# AVR.net
KiCad netlist of a schematic drawn in Altium Designer
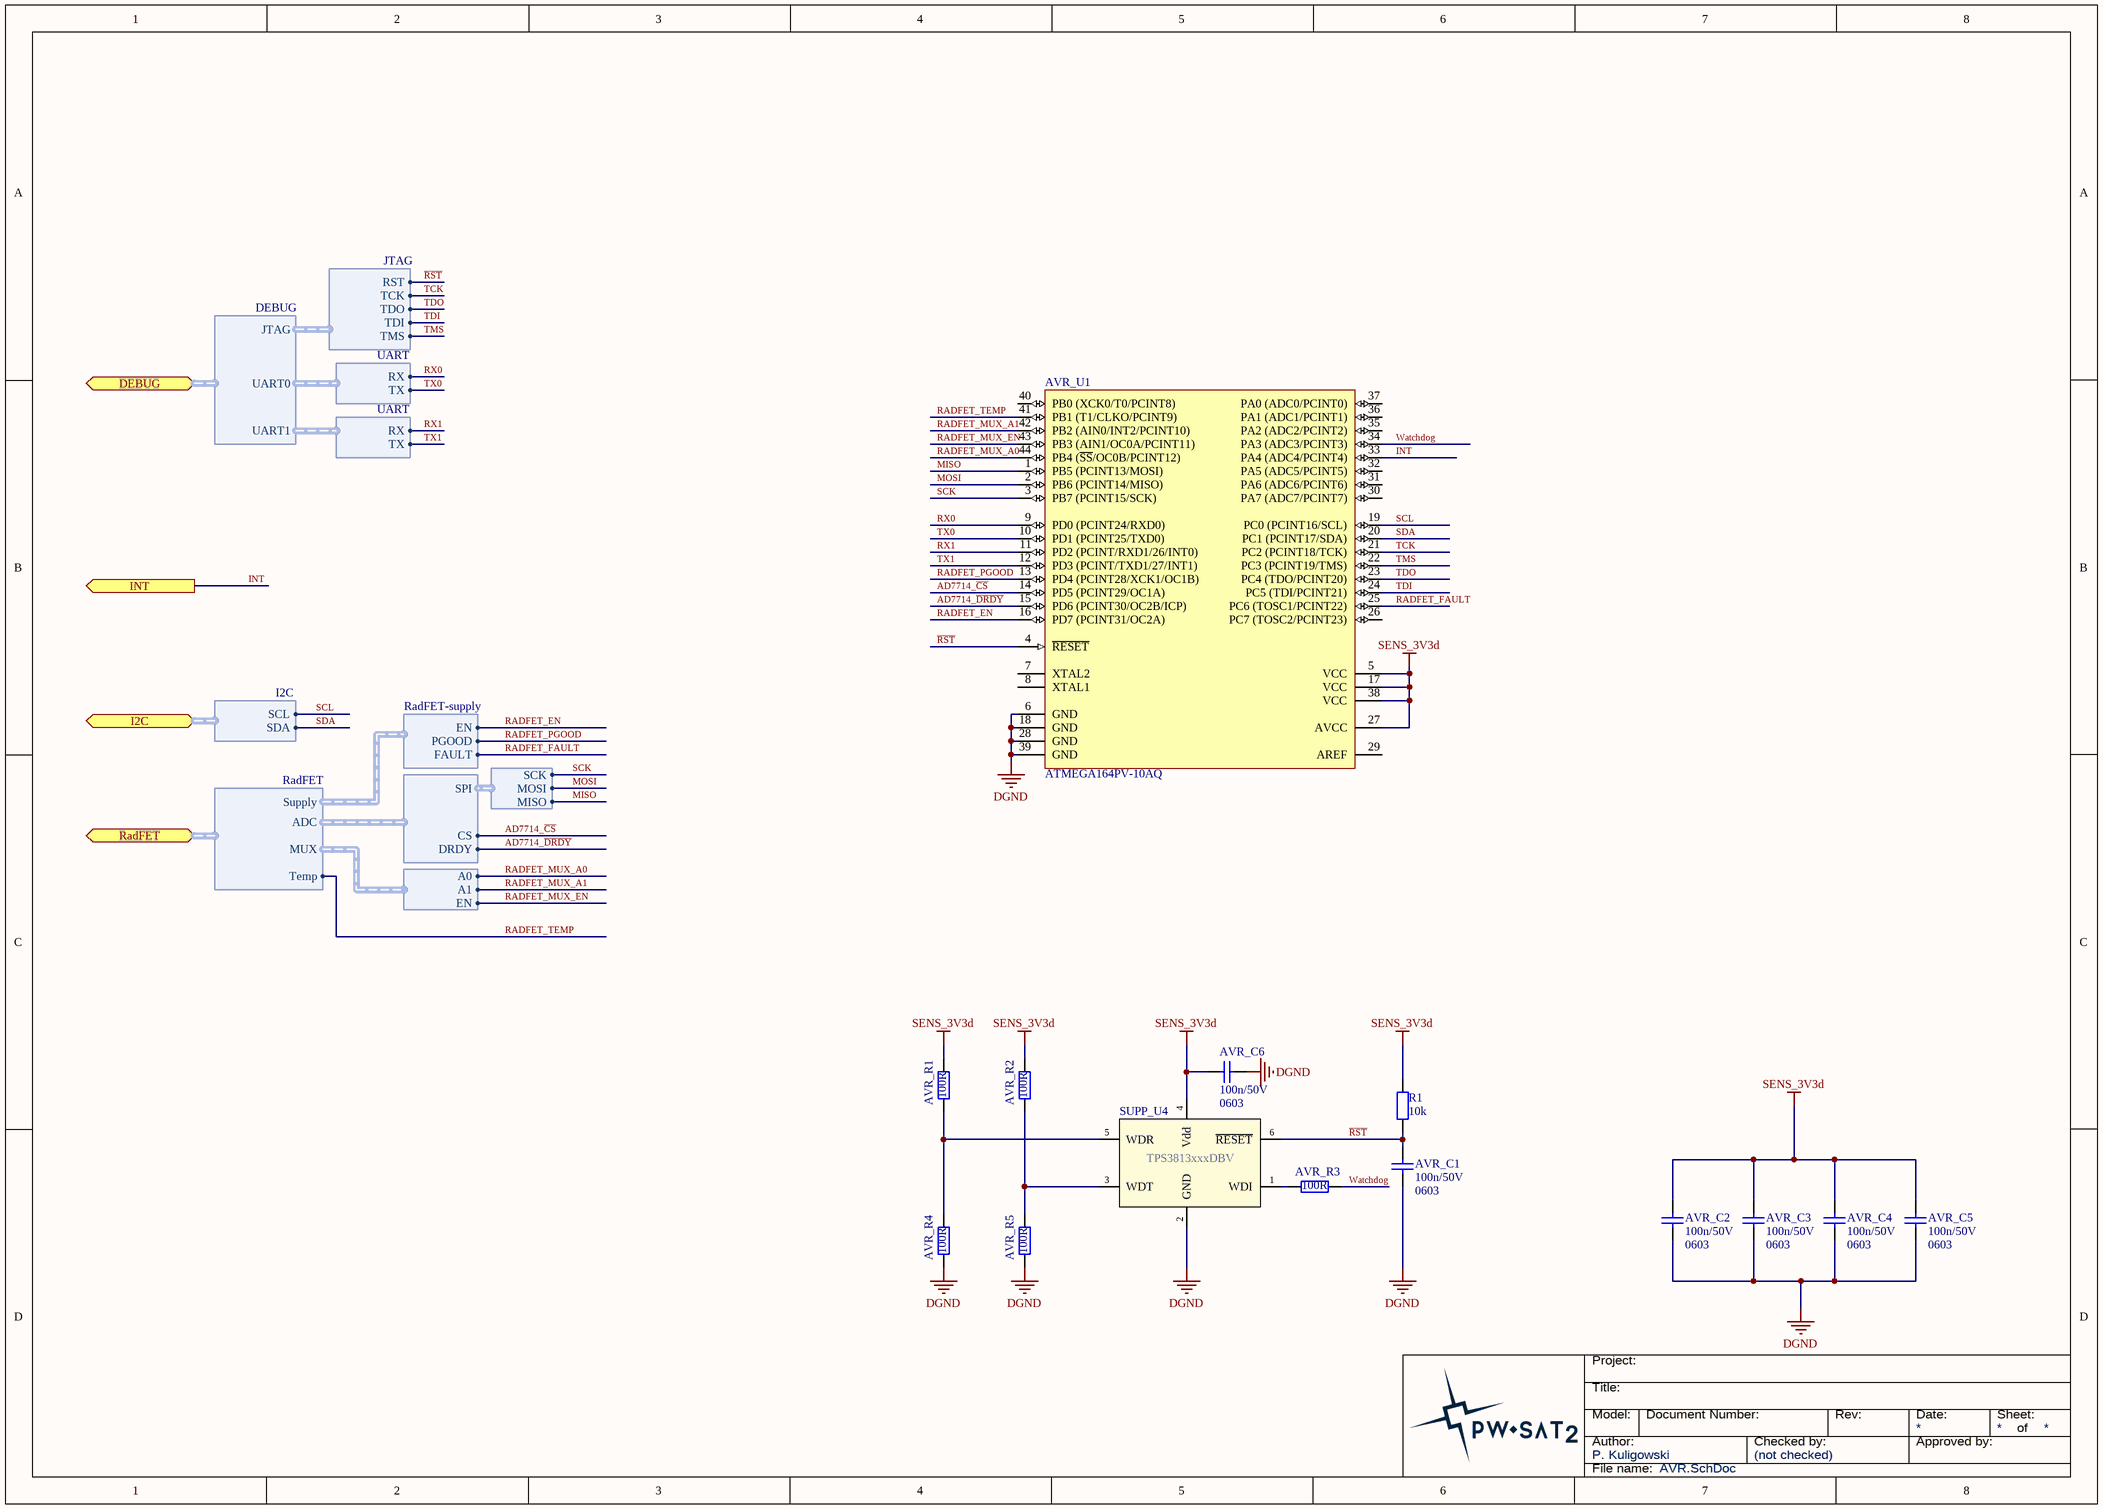
[diagram p0: AVR.SchDoc]

(export (version "E")
  (design (tool "Eeschema 10.0.6"))
  (components
    (comp (ref "AVR_C1")
      (value "100n/50V")
      (footprint "SMD_Capacitor_0603")
      (description "Ceramic Cap Kemet COTS 100n/50V X7R 0603")
      (fields
        (field (name "MANUFACTURER") "Kemet")
        (field (name "MANUFACTURERPARTNUMBER") "C0603T104K5RALTU")
        (field (name "PACKAGE") "0603")
      )
      (libsource (lib "capacitors") (part "Cer_C0603T104K5RALTU"))
    )
    (comp (ref "AVR_C2")
      (value "100n/50V")
      (footprint "SMD_Capacitor_0603")
      (description "Ceramic Cap Kemet COTS 100n/50V X7R 0603")
      (fields
        (field (name "MANUFACTURER") "Kemet")
        (field (name "MANUFACTURERPARTNUMBER") "C0603T104K5RALTU")
        (field (name "PACKAGE") "0603")
      )
      (libsource (lib "capacitors") (part "Cer_C0603T104K5RALTU"))
    )
    (comp (ref "AVR_C3")
      (value "100n/50V")
      (footprint "SMD_Capacitor_0603")
      (description "Ceramic Cap Kemet COTS 100n/50V X7R 0603")
      (fields
        (field (name "MANUFACTURER") "Kemet")
        (field (name "MANUFACTURERPARTNUMBER") "C0603T104K5RALTU")
        (field (name "PACKAGE") "0603")
      )
      (libsource (lib "capacitors") (part "Cer_C0603T104K5RALTU"))
    )
    (comp (ref "AVR_C4")
      (value "100n/50V")
      (footprint "SMD_Capacitor_0603")
      (description "Ceramic Cap Kemet COTS 100n/50V X7R 0603")
      (fields
        (field (name "MANUFACTURER") "Kemet")
        (field (name "MANUFACTURERPARTNUMBER") "C0603T104K5RALTU")
        (field (name "PACKAGE") "0603")
      )
      (libsource (lib "capacitors") (part "Cer_C0603T104K5RALTU"))
    )
    (comp (ref "AVR_C5")
      (value "100n/50V")
      (footprint "SMD_Capacitor_0603")
      (description "Ceramic Cap Kemet COTS 100n/50V X7R 0603")
      (fields
        (field (name "MANUFACTURER") "Kemet")
        (field (name "MANUFACTURERPARTNUMBER") "C0603T104K5RALTU")
        (field (name "PACKAGE") "0603")
      )
      (libsource (lib "capacitors") (part "Cer_C0603T104K5RALTU"))
    )
    (comp (ref "AVR_C6")
      (value "100n/50V")
      (footprint "SMD_Capacitor_0603")
      (description "Ceramic Cap Kemet COTS 100n/50V X7R 0603")
      (fields
        (field (name "MANUFACTURER") "Kemet")
        (field (name "MANUFACTURERPARTNUMBER") "C0603T104K5RALTU")
        (field (name "PACKAGE") "0603")
      )
      (libsource (lib "capacitors") (part "Cer_C0603T104K5RALTU"))
    )
    (comp (ref "AVR_R1")
      (value "100R")
      (footprint "SMD_Resistor_0603")
      (libsource (lib "resistors") (part "Res"))
    )
    (comp (ref "AVR_R2")
      (value "100R")
      (footprint "SMD_Resistor_0603")
      (libsource (lib "resistors") (part "Res"))
    )
    (comp (ref "AVR_R3") (value "100R") (footprint "SMD_Resistor_0603") (libsource (lib "") (part "Res_1")))
    (comp (ref "AVR_R4")
      (value "100R")
      (footprint "SMD_Resistor_0603")
      (libsource (lib "resistors") (part "Res"))
    )
    (comp (ref "AVR_R5")
      (value "100R")
      (footprint "SMD_Resistor_0603")
      (libsource (lib "resistors") (part "Res"))
    )
    (comp (ref "AVR_U1")
      (value "ATMEGA164PV-10AQ")
      (footprint "TQFP-44")
      (description "General-purpose microcontroller")
      (libsource (lib "microcircuits") (part "ATMEGA164PV-10AQ"))
    )
    (comp (ref "R1")
      (value "10k")
      (footprint "SMD_Resistor_0603")
      (description "10k/1% Vishay CRCW 0603 Resistor. 100mW, 100ppm, 75V.")
      (fields
        (field (name "MANUFACTURER") "Vishay")
        (field (name "MANUFACTURERPARTNUMBER") "CRCW060310K0FKxxxx")
      )
      (libsource (lib "resistors") (part "CRCW060310K0FKxxxx"))
    )
    (comp (ref "SUPP_U4")
      (value "TPS3813xxxDBV")
      (footprint "SOT23-6")
      (description "Processor Supervisory Circuits with Window-Watchdog.")
      (fields (field (name "MANUFACTURER") "Texas Instruments"))
      (libsource (lib "microcircuits") (part "TPS3813xxxDBV"))
    )
  )
  (nets
    (net (code "10") (name "/AD7714_~{CS}") (class "Default")
      (node (ref "AVR_U1") (pin "14") (pinfunction "PD5_(PCINT29/OC1A)_14") (pintype "bidirectional"))
    )
    (net (code "11") (name "/AD7714_~{DRDY}") (class "Default")
      (node (ref "AVR_U1") (pin "15") (pinfunction "PD6_(PCINT30/OC2B/ICP)_15") (pintype "bidirectional"))
    )
    (net (code "13") (name "/INT") (class "Default")
      (node (ref "AVR_U1") (pin "33") (pinfunction "PA4_(ADC4/PCINT4)_33") (pintype "bidirectional"))
    )
    (net (code "14") (name "/MISO") (class "Default")
      (node (ref "AVR_U1") (pin "1") (pinfunction "PB5_(PCINT13/MOSI)_1") (pintype "bidirectional"))
    )
    (net (code "15") (name "/MOSI") (class "Default")
      (node (ref "AVR_U1") (pin "2") (pinfunction "PB6_(PCINT14/MISO)_2") (pintype "bidirectional"))
    )
    (net (code "16") (name "/RADFET_EN") (class "Default")
      (node (ref "AVR_U1") (pin "16") (pinfunction "PD7_(PCINT31/OC2A)_16") (pintype "bidirectional"))
    )
    (net (code "17") (name "/RADFET_FAULT") (class "Default")
      (node (ref "AVR_U1") (pin "25") (pinfunction "PC6_(TOSC1/PCINT22)_25") (pintype "bidirectional"))
    )
    (net (code "18") (name "/RADFET_MUX_A0") (class "Default")
      (node (ref "AVR_U1") (pin "44") (pinfunction "PB4_(~{SS}/OC0B/PCINT12)_44") (pintype "bidirectional"))
    )
    (net (code "19") (name "/RADFET_MUX_A1") (class "Default")
      (node (ref "AVR_U1") (pin "42") (pinfunction "PB2_(AIN0/INT2/PCINT10)_42") (pintype "bidirectional"))
    )
    (net (code "20") (name "/RADFET_MUX_EN") (class "Default")
      (node (ref "AVR_U1") (pin "43") (pinfunction "PB3_(AIN1/OC0A/PCINT11)_43") (pintype "bidirectional"))
    )
    (net (code "21") (name "/RADFET_PGOOD") (class "Default")
      (node (ref "AVR_U1") (pin "13") (pinfunction "PD4_(PCINT28/XCK1/OC1B)_13") (pintype "bidirectional"))
    )
    (net (code "22") (name "/RADFET_TEMP") (class "Default")
      (node (ref "AVR_U1") (pin "41") (pinfunction "PB1_(T1/CLKO/PCINT9)_41") (pintype "bidirectional"))
    )
    (net (code "23") (name "/RX0") (class "Default")
      (node (ref "AVR_U1") (pin "9") (pinfunction "PD0_(PCINT24/RXD0)_9") (pintype "bidirectional"))
    )
    (net (code "24") (name "/RX1") (class "Default")
      (node (ref "AVR_U1") (pin "11") (pinfunction "PD2_(PCINT/RXD1/26/INT0)_11") (pintype "bidirectional"))
    )
    (net (code "26") (name "/SCK") (class "Default")
      (node (ref "AVR_U1") (pin "3") (pinfunction "PB7_(PCINT15/SCK)_3") (pintype "bidirectional"))
    )
    (net (code "27") (name "/SCL") (class "Default")
      (node (ref "AVR_U1") (pin "19") (pinfunction "PC0_(PCINT16/SCL)_19") (pintype "bidirectional"))
    )
    (net (code "28") (name "/SDA") (class "Default")
      (node (ref "AVR_U1") (pin "20") (pinfunction "PC1_(PCINT17/SDA)_20") (pintype "bidirectional"))
    )
    (net (code "29") (name "/TCK") (class "Default")
      (node (ref "AVR_U1") (pin "21") (pinfunction "PC2_(PCINT18/TCK)_21") (pintype "bidirectional"))
    )
    (net (code "30") (name "/TDI") (class "Default")
      (node (ref "AVR_U1") (pin "24") (pinfunction "PC5_(TDI/PCINT21)_24") (pintype "bidirectional"))
    )
    (net (code "31") (name "/TDO") (class "Default")
      (node (ref "AVR_U1") (pin "23") (pinfunction "PC4_(TDO/PCINT20)_23") (pintype "bidirectional"))
    )
    (net (code "32") (name "/TMS") (class "Default")
      (node (ref "AVR_U1") (pin "22") (pinfunction "PC3_(PCINT19/TMS)_22") (pintype "bidirectional"))
    )
    (net (code "33") (name "/TX0") (class "Default")
      (node (ref "AVR_U1") (pin "10") (pinfunction "PD1_(PCINT25/TXD0)_10") (pintype "bidirectional"))
    )
    (net (code "34") (name "/TX1") (class "Default")
      (node (ref "AVR_U1") (pin "12") (pinfunction "PD3_(PCINT/TXD1/27/INT1)_12") (pintype "bidirectional"))
    )
    (net (code "35") (name "/Watchdog") (class "Default")
      (node (ref "AVR_R3") (pin "2") (pinfunction "2_2") (pintype "passive"))
      (node (ref "AVR_U1") (pin "34") (pinfunction "PA3_(ADC3/PCINT3)_34") (pintype "bidirectional"))
    )
    (net (code "43") (name "/~{RST}") (class "Default")
      (node (ref "AVR_C1") (pin "1") (pinfunction "1_1") (pintype "passive"))
      (node (ref "AVR_U1") (pin "4") (pinfunction "~{RESET}_4") (pintype "input"))
      (node (ref "R1") (pin "2") (pinfunction "2_2") (pintype "passive"))
      (node (ref "SUPP_U4") (pin "6") (pinfunction "~{RESET}_6") (pintype "passive"))
    )
    (net (code "44") (name "DGND") (class "Default")
      (node (ref "AVR_C1") (pin "2") (pinfunction "2_2") (pintype "passive"))
      (node (ref "AVR_C2") (pin "2") (pinfunction "2_2") (pintype "passive"))
      (node (ref "AVR_C3") (pin "2") (pinfunction "2_2") (pintype "passive"))
      (node (ref "AVR_C4") (pin "2") (pinfunction "2_2") (pintype "passive"))
      (node (ref "AVR_C5") (pin "2") (pinfunction "2_2") (pintype "passive"))
      (node (ref "AVR_C6") (pin "2") (pinfunction "2_2") (pintype "passive"))
      (node (ref "AVR_R4") (pin "2") (pinfunction "2_2") (pintype "passive"))
      (node (ref "AVR_R5") (pin "2") (pinfunction "2_2") (pintype "passive"))
      (node (ref "AVR_U1") (pin "18") (pinfunction "GND_18") (pintype "power_in"))
      (node (ref "AVR_U1") (pin "28") (pinfunction "GND_28") (pintype "power_in"))
      (node (ref "AVR_U1") (pin "39") (pinfunction "GND_39") (pintype "power_in"))
      (node (ref "AVR_U1") (pin "6") (pinfunction "GND_6") (pintype "power_in"))
      (node (ref "SUPP_U4") (pin "2") (pinfunction "GND_2") (pintype "passive"))
    )
    (net (code "45") (name "Net-(SUPP_U4-WDI)") (class "Default")
      (node (ref "AVR_R3") (pin "1") (pinfunction "1_1") (pintype "passive"))
      (node (ref "SUPP_U4") (pin "1") (pinfunction "WDI_1") (pintype "passive"))
    )
    (net (code "46") (name "Net-(SUPP_U4-WDR)") (class "Default")
      (node (ref "AVR_R1") (pin "2") (pinfunction "2_2") (pintype "passive"))
      (node (ref "AVR_R4") (pin "1") (pinfunction "1_1") (pintype "passive"))
      (node (ref "SUPP_U4") (pin "5") (pinfunction "WDR_5") (pintype "passive"))
    )
    (net (code "47") (name "Net-(SUPP_U4-WDT)") (class "Default")
      (node (ref "AVR_R2") (pin "2") (pinfunction "2_2") (pintype "passive"))
      (node (ref "AVR_R5") (pin "1") (pinfunction "1_1") (pintype "passive"))
      (node (ref "SUPP_U4") (pin "3") (pinfunction "WDT_3") (pintype "passive"))
    )
    (net (code "48") (name "SENS_3V3d") (class "Default")
      (node (ref "AVR_C2") (pin "1") (pinfunction "1_1") (pintype "passive"))
      (node (ref "AVR_C3") (pin "1") (pinfunction "1_1") (pintype "passive"))
      (node (ref "AVR_C4") (pin "1") (pinfunction "1_1") (pintype "passive"))
      (node (ref "AVR_C5") (pin "1") (pinfunction "1_1") (pintype "passive"))
      (node (ref "AVR_C6") (pin "1") (pinfunction "1_1") (pintype "passive"))
      (node (ref "AVR_R1") (pin "1") (pinfunction "1_1") (pintype "passive"))
      (node (ref "AVR_R2") (pin "1") (pinfunction "1_1") (pintype "passive"))
      (node (ref "AVR_U1") (pin "17") (pinfunction "VCC_17") (pintype "power_in"))
      (node (ref "AVR_U1") (pin "27") (pinfunction "AVCC_27") (pintype "power_in"))
      (node (ref "AVR_U1") (pin "38") (pinfunction "VCC_38") (pintype "power_in"))
      (node (ref "AVR_U1") (pin "5") (pinfunction "VCC_5") (pintype "power_in"))
      (node (ref "R1") (pin "1") (pinfunction "1_1") (pintype "passive"))
      (node (ref "SUPP_U4") (pin "4") (pinfunction "Vdd_4") (pintype "passive"))
    )
    (net (code "49") (name "unconnected-(AVR_U1-AREF-Pad29)") (class "Default")
      (node (ref "AVR_U1") (pin "29") (pinfunction "AREF_29") (pintype "power_in"))
    )
    (net (code "50") (name "unconnected-(AVR_U1-PA0_(ADC0{slash}PCINT0)-Pad37)") (class "Default")
      (node (ref "AVR_U1") (pin "37") (pinfunction "PA0_(ADC0/PCINT0)_37") (pintype "bidirectional"))
    )
    (net (code "51") (name "unconnected-(AVR_U1-PA1_(ADC1{slash}PCINT1)-Pad36)") (class "Default")
      (node (ref "AVR_U1") (pin "36") (pinfunction "PA1_(ADC1/PCINT1)_36") (pintype "bidirectional"))
    )
    (net (code "52") (name "unconnected-(AVR_U1-PA2_(ADC2{slash}PCINT2)-Pad35)") (class "Default")
      (node (ref "AVR_U1") (pin "35") (pinfunction "PA2_(ADC2/PCINT2)_35") (pintype "bidirectional"))
    )
    (net (code "53") (name "unconnected-(AVR_U1-PA5_(ADC5{slash}PCINT5)-Pad32)") (class "Default")
      (node (ref "AVR_U1") (pin "32") (pinfunction "PA5_(ADC5/PCINT5)_32") (pintype "bidirectional"))
    )
    (net (code "54") (name "unconnected-(AVR_U1-PA6_(ADC6{slash}PCINT6)-Pad31)") (class "Default")
      (node (ref "AVR_U1") (pin "31") (pinfunction "PA6_(ADC6/PCINT6)_31") (pintype "bidirectional"))
    )
    (net (code "55") (name "unconnected-(AVR_U1-PA7_(ADC7{slash}PCINT7)-Pad30)") (class "Default")
      (node (ref "AVR_U1") (pin "30") (pinfunction "PA7_(ADC7/PCINT7)_30") (pintype "bidirectional"))
    )
    (net (code "56") (name "unconnected-(AVR_U1-PB0_(XCK0{slash}T0{slash}PCINT8)-Pad40)") (class "Default")
      (node (ref "AVR_U1") (pin "40") (pinfunction "PB0_(XCK0/T0/PCINT8)_40") (pintype "bidirectional"))
    )
    (net (code "57") (name "unconnected-(AVR_U1-PC7_(TOSC2{slash}PCINT23)-Pad26)") (class "Default")
      (node (ref "AVR_U1") (pin "26") (pinfunction "PC7_(TOSC2/PCINT23)_26") (pintype "bidirectional"))
    )
    (net (code "58") (name "unconnected-(AVR_U1-XTAL1-Pad8)") (class "Default")
      (node (ref "AVR_U1") (pin "8") (pinfunction "XTAL1_8") (pintype "passive"))
    )
    (net (code "59") (name "unconnected-(AVR_U1-XTAL2-Pad7)") (class "Default")
      (node (ref "AVR_U1") (pin "7") (pinfunction "XTAL2_7") (pintype "passive"))
    )
  )
)
